# INTERFACE.net
KiCad netlist of a schematic drawn in EAGLE
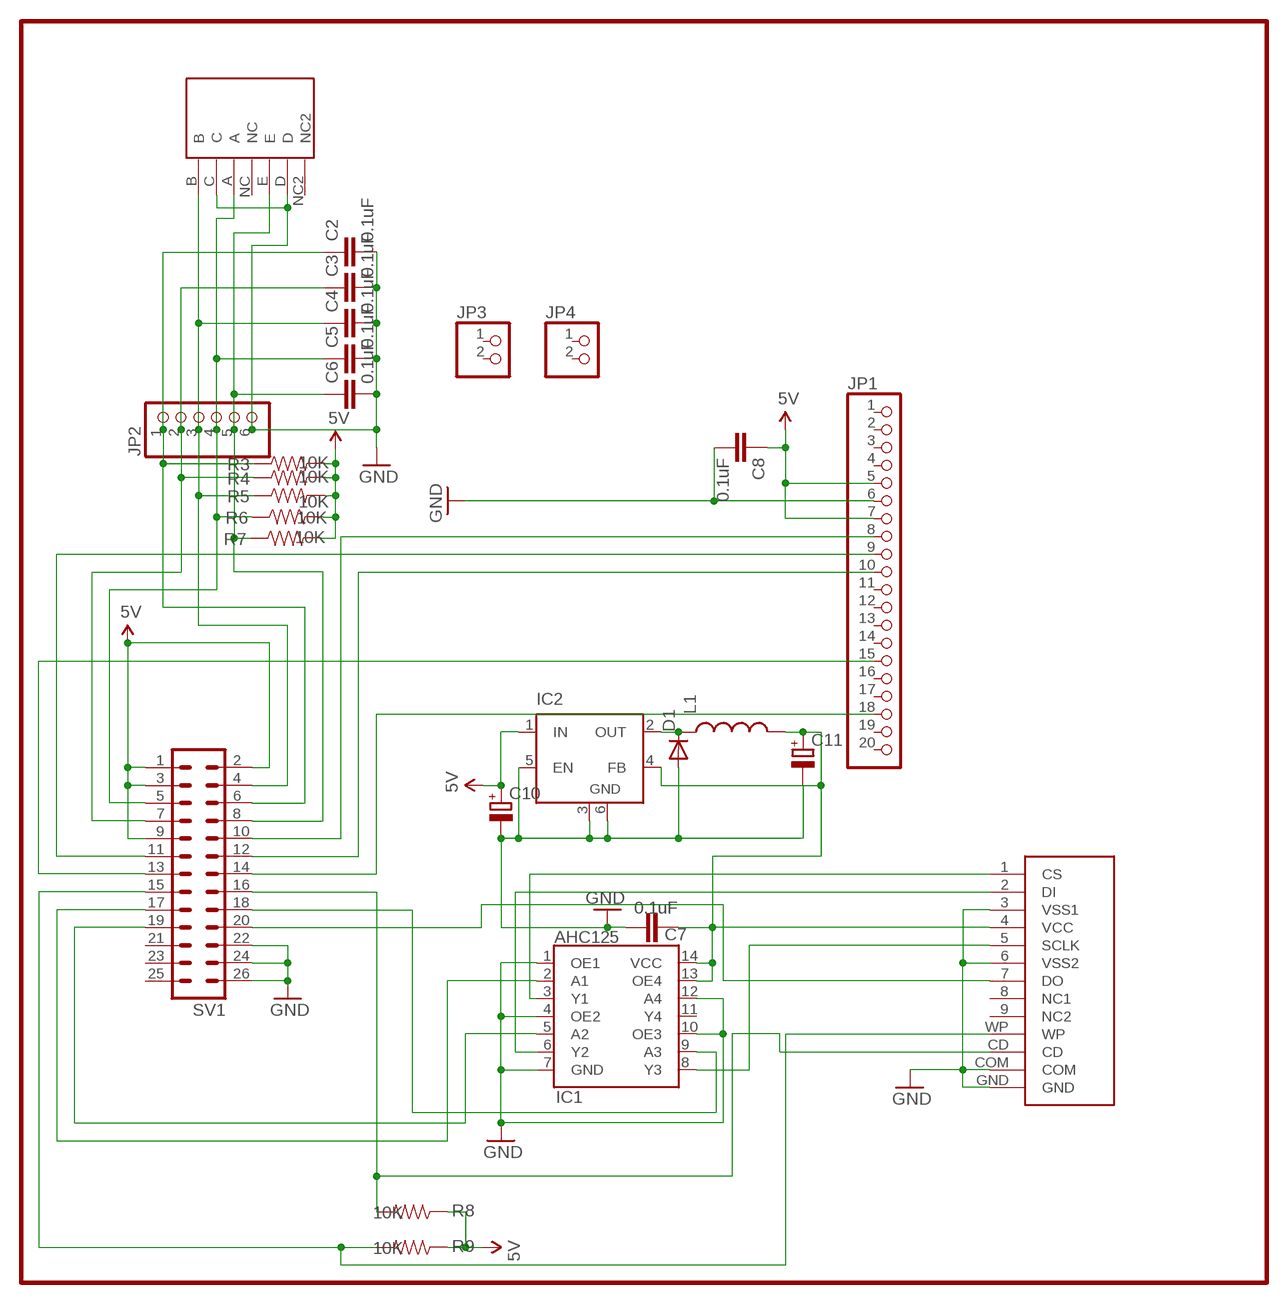
[diagram p0: schematic, sheet 1]

(export (version "E")
  (design (tool "Eeschema 10.0.6"))
  (components
    (comp (ref "C2")
      (value "0.1uF")
      (footprint "eagle-import:0805")
      (libsource (lib "eagle-import") (part "CAP0805"))
    )
    (comp (ref "C3")
      (value "0.1uF")
      (footprint "eagle-import:0805")
      (libsource (lib "eagle-import") (part "CAP0805"))
    )
    (comp (ref "C4")
      (value "0.1uF")
      (footprint "eagle-import:0805")
      (libsource (lib "eagle-import") (part "CAP0805"))
    )
    (comp (ref "C5")
      (value "0.1uF")
      (footprint "eagle-import:0805")
      (libsource (lib "eagle-import") (part "CAP0805"))
    )
    (comp (ref "C6")
      (value "0.1uF")
      (footprint "eagle-import:0805")
      (libsource (lib "eagle-import") (part "CAP0805"))
    )
    (comp (ref "C7")
      (value "0.1uF")
      (footprint "eagle-import:0805")
      (libsource (lib "eagle-import") (part "CAP0805"))
    )
    (comp (ref "C8")
      (value "0.1uF")
      (footprint "eagle-import:0805")
      (libsource (lib "eagle-import") (part "CAP0805"))
    )
    (comp (ref "C10")
      (value "CPOL-EUE3.5-8")
      (footprint "eagle-import:E3,5-8")
      (libsource (lib "eagle-import") (part "CPOL-EUE3.5-8"))
    )
    (comp (ref "C11")
      (value "CPOL-EUE3.5-8")
      (footprint "eagle-import:E3,5-8")
      (libsource (lib "eagle-import") (part "CPOL-EUE3.5-8"))
    )
    (comp (ref "D1")
      (value "DIODESMB")
      (footprint "eagle-import:SMB-DIODE")
      (libsource (lib "eagle-import") (part "DIODESMB"))
    )
    (comp (ref "IC1")
      (value "AHC125")
      (footprint "eagle-import:DIN14")
      (libsource (lib "eagle-import") (part "AHC125"))
    )
    (comp (ref "IC2")
      (value "LM2596S")
      (footprint "eagle-import:TO263-5")
      (libsource (lib "eagle-import") (part "LM2596S"))
    )
    (comp (ref "JP1")
      (value "PINHD-1X20")
      (footprint "eagle-import:1X20")
      (libsource (lib "eagle-import") (part "PINHD-1X20"))
    )
    (comp (ref "JP2")
      (value "PINHD-1X6")
      (footprint "eagle-import:1X06")
      (libsource (lib "eagle-import") (part "PINHD-1X6"))
    )
    (comp (ref "JP3")
      (value "PINHD-1X2")
      (footprint "eagle-import:1X02")
      (libsource (lib "eagle-import") (part "PINHD-1X2"))
    )
    (comp (ref "JP4")
      (value "PINHD-1X2")
      (footprint "eagle-import:1X02")
      (libsource (lib "eagle-import") (part "PINHD-1X2"))
    )
    (comp (ref "L1")
      (value "INDUCTORPWR")
      (footprint "eagle-import:CDRH125")
      (libsource (lib "eagle-import") (part "INDUCTORPWR"))
    )
    (comp (ref "Q2")
      (value "SDCARD")
      (footprint "eagle-import:SDCARD")
      (libsource (lib "eagle-import") (part "SDCARD"))
    )
    (comp (ref "R3")
      (value "10K")
      (footprint "eagle-import:0805")
      (libsource (lib "eagle-import") (part "RESISTOR"))
    )
    (comp (ref "R4")
      (value "10K")
      (footprint "eagle-import:0805")
      (libsource (lib "eagle-import") (part "RESISTOR"))
    )
    (comp (ref "R5")
      (value "10K")
      (footprint "eagle-import:0805")
      (libsource (lib "eagle-import") (part "RESISTOR"))
    )
    (comp (ref "R6")
      (value "10K")
      (footprint "eagle-import:0805")
      (libsource (lib "eagle-import") (part "RESISTOR"))
    )
    (comp (ref "R7")
      (value "10K")
      (footprint "eagle-import:0805")
      (libsource (lib "eagle-import") (part "RESISTOR"))
    )
    (comp (ref "R8")
      (value "10K")
      (footprint "eagle-import:0805")
      (libsource (lib "eagle-import") (part "RESISTOR"))
    )
    (comp (ref "R9")
      (value "10K")
      (footprint "eagle-import:0805")
      (libsource (lib "eagle-import") (part "RESISTOR"))
    )
    (comp (ref "S2")
      (value "DJFS")
      (footprint "eagle-import:PIN5")
      (libsource (lib "eagle-import") (part "DJFS"))
    )
    (comp (ref "SV1")
      (value "ML26")
      (footprint "eagle-import:ML26")
      (libsource (lib "eagle-import") (part "ML26"))
    )
  )
  (nets
    (net (code "1") (name "5V") (class "Default")
      (node (ref "C10") (pin "+") (pinfunction "+_+") (pintype "passive"))
      (node (ref "C8") (pin "1") (pinfunction "1_1") (pintype "passive"))
      (node (ref "IC2") (pin "1") (pinfunction "IN_1") (pintype "input"))
      (node (ref "JP1") (pin "5") (pinfunction "5_5") (pintype "passive"))
      (node (ref "JP1") (pin "7") (pinfunction "7_7") (pintype "passive"))
      (node (ref "R3") (pin "2") (pinfunction "2_2") (pintype "passive"))
      (node (ref "R4") (pin "2") (pinfunction "2_2") (pintype "passive"))
      (node (ref "R5") (pin "2") (pinfunction "2_2") (pintype "passive"))
      (node (ref "R6") (pin "2") (pinfunction "2_2") (pintype "passive"))
      (node (ref "R7") (pin "2") (pinfunction "2_2") (pintype "passive"))
      (node (ref "R8") (pin "1") (pinfunction "1_1") (pintype "passive"))
      (node (ref "R9") (pin "1") (pinfunction "1_1") (pintype "passive"))
      (node (ref "SV1") (pin "1") (pinfunction "1_1") (pintype "passive"))
      (node (ref "SV1") (pin "2") (pinfunction "2_2") (pintype "passive"))
      (node (ref "SV1") (pin "3") (pinfunction "3_3") (pintype "passive"))
      (node (ref "SV1") (pin "9") (pinfunction "9_9") (pintype "passive"))
    )
    (net (code "2") (name "GND") (class "Default")
      (node (ref "C10") (pin "-") (pinfunction "-_-") (pintype "passive"))
      (node (ref "C11") (pin "-") (pinfunction "-_-") (pintype "passive"))
      (node (ref "C2") (pin "2") (pinfunction "2_2") (pintype "passive"))
      (node (ref "C3") (pin "2") (pinfunction "2_2") (pintype "passive"))
      (node (ref "C4") (pin "2") (pinfunction "2_2") (pintype "passive"))
      (node (ref "C5") (pin "2") (pinfunction "2_2") (pintype "passive"))
      (node (ref "C6") (pin "2") (pinfunction "2_2") (pintype "passive"))
      (node (ref "C7") (pin "2") (pinfunction "2_2") (pintype "passive"))
      (node (ref "C8") (pin "2") (pinfunction "2_2") (pintype "passive"))
      (node (ref "D1") (pin "A") (pinfunction "A_A") (pintype "passive"))
      (node (ref "IC1") (pin "1") (pinfunction "OE1_1") (pintype "input"))
      (node (ref "IC1") (pin "10") (pinfunction "OE3_10") (pintype "input"))
      (node (ref "IC1") (pin "12") (pinfunction "A4_12") (pintype "input"))
      (node (ref "IC1") (pin "4") (pinfunction "OE2_4") (pintype "input"))
      (node (ref "IC1") (pin "7") (pinfunction "GND_7") (pintype "power_in"))
      (node (ref "IC2") (pin "3") (pinfunction "GND_3") (pintype "power_in"))
      (node (ref "IC2") (pin "5") (pinfunction "EN_5") (pintype "input"))
      (node (ref "IC2") (pin "6") (pinfunction "GND_6") (pintype "power_in"))
      (node (ref "JP1") (pin "6") (pinfunction "6_6") (pintype "passive"))
      (node (ref "JP2") (pin "6") (pinfunction "6_6") (pintype "passive"))
      (node (ref "Q2") (pin "3") (pinfunction "VSS1_3") (pintype "bidirectional"))
      (node (ref "Q2") (pin "6") (pinfunction "VSS2_6") (pintype "bidirectional"))
      (node (ref "Q2") (pin "COM") (pinfunction "COM_COM") (pintype "bidirectional"))
      (node (ref "Q2") (pin "GND") (pinfunction "GND_GND") (pintype "power_in"))
      (node (ref "S2") (pin "C") (pinfunction "C_C") (pintype "bidirectional"))
      (node (ref "S2") (pin "D") (pinfunction "D_D") (pintype "bidirectional"))
      (node (ref "SV1") (pin "22") (pinfunction "22_22") (pintype "passive"))
      (node (ref "SV1") (pin "24") (pinfunction "24_24") (pintype "passive"))
      (node (ref "SV1") (pin "26") (pinfunction "26_26") (pintype "passive"))
    )
    (net (code "3") (name "Net-(C2-Pad1)") (class "Default")
      (node (ref "C2") (pin "1") (pinfunction "1_1") (pintype "passive"))
      (node (ref "JP2") (pin "1") (pinfunction "1_1") (pintype "passive"))
      (node (ref "R3") (pin "1") (pinfunction "1_1") (pintype "passive"))
      (node (ref "SV1") (pin "6") (pinfunction "6_6") (pintype "passive"))
    )
    (net (code "4") (name "Net-(C3-Pad1)") (class "Default")
      (node (ref "C3") (pin "1") (pinfunction "1_1") (pintype "passive"))
      (node (ref "JP2") (pin "2") (pinfunction "2_2") (pintype "passive"))
      (node (ref "R4") (pin "1") (pinfunction "1_1") (pintype "passive"))
      (node (ref "SV1") (pin "7") (pinfunction "7_7") (pintype "passive"))
    )
    (net (code "5") (name "Net-(C4-Pad1)") (class "Default")
      (node (ref "C4") (pin "1") (pinfunction "1_1") (pintype "passive"))
      (node (ref "JP2") (pin "3") (pinfunction "3_3") (pintype "passive"))
      (node (ref "R5") (pin "1") (pinfunction "1_1") (pintype "passive"))
      (node (ref "S2") (pin "B") (pinfunction "B_B") (pintype "bidirectional"))
      (node (ref "SV1") (pin "4") (pinfunction "4_4") (pintype "passive"))
    )
    (net (code "6") (name "Net-(C5-Pad1)") (class "Default")
      (node (ref "C5") (pin "1") (pinfunction "1_1") (pintype "passive"))
      (node (ref "JP2") (pin "4") (pinfunction "4_4") (pintype "passive"))
      (node (ref "R6") (pin "1") (pinfunction "1_1") (pintype "passive"))
      (node (ref "S2") (pin "A") (pinfunction "A_A") (pintype "bidirectional"))
      (node (ref "SV1") (pin "5") (pinfunction "5_5") (pintype "passive"))
    )
    (net (code "7") (name "Net-(C6-Pad1)") (class "Default")
      (node (ref "C6") (pin "1") (pinfunction "1_1") (pintype "passive"))
      (node (ref "JP2") (pin "5") (pinfunction "5_5") (pintype "passive"))
      (node (ref "R7") (pin "1") (pinfunction "1_1") (pintype "passive"))
      (node (ref "S2") (pin "E") (pinfunction "E_E") (pintype "bidirectional"))
      (node (ref "SV1") (pin "8") (pinfunction "8_8") (pintype "passive"))
    )
    (net (code "8") (name "Net-(IC1-A1)") (class "Default")
      (node (ref "IC1") (pin "2") (pinfunction "A1_2") (pintype "input"))
      (node (ref "SV1") (pin "17") (pinfunction "17_17") (pintype "passive"))
    )
    (net (code "9") (name "Net-(IC1-A2)") (class "Default")
      (node (ref "IC1") (pin "5") (pinfunction "A2_5") (pintype "input"))
      (node (ref "SV1") (pin "19") (pinfunction "19_19") (pintype "passive"))
    )
    (net (code "10") (name "Net-(IC1-A3)") (class "Default")
      (node (ref "IC1") (pin "9") (pinfunction "A3_9") (pintype "input"))
      (node (ref "SV1") (pin "18") (pinfunction "18_18") (pintype "passive"))
    )
    (net (code "11") (name "Net-(IC1-OE4)") (class "Default")
      (node (ref "C11") (pin "+") (pinfunction "+_+") (pintype "passive"))
      (node (ref "C7") (pin "1") (pinfunction "1_1") (pintype "passive"))
      (node (ref "IC1") (pin "13") (pinfunction "OE4_13") (pintype "input"))
      (node (ref "IC1") (pin "14") (pinfunction "VCC_14") (pintype "power_in"))
      (node (ref "IC2") (pin "4") (pinfunction "FB_4") (pintype "input"))
      (node (ref "L1") (pin "2") (pinfunction "2_2") (pintype "passive"))
      (node (ref "Q2") (pin "4") (pinfunction "VCC_4") (pintype "power_in"))
    )
    (net (code "12") (name "Net-(IC1-Y1)") (class "Default")
      (node (ref "IC1") (pin "3") (pinfunction "Y1_3") (pintype "output"))
      (node (ref "Q2") (pin "1") (pinfunction "CS_1") (pintype "bidirectional"))
    )
    (net (code "13") (name "Net-(IC1-Y2)") (class "Default")
      (node (ref "IC1") (pin "6") (pinfunction "Y2_6") (pintype "output"))
      (node (ref "Q2") (pin "2") (pinfunction "DI_2") (pintype "bidirectional"))
    )
    (net (code "14") (name "Net-(IC1-Y3)") (class "Default")
      (node (ref "IC1") (pin "8") (pinfunction "Y3_8") (pintype "output"))
      (node (ref "Q2") (pin "5") (pinfunction "SCLK_5") (pintype "bidirectional"))
    )
    (net (code "15") (name "Net-(IC2-OUT)") (class "Default")
      (node (ref "D1") (pin "C") (pinfunction "C_C") (pintype "passive"))
      (node (ref "IC2") (pin "2") (pinfunction "OUT_2") (pintype "output"))
      (node (ref "L1") (pin "1") (pinfunction "1_1") (pintype "passive"))
    )
    (net (code "16") (name "Net-(JP1-Pad8)") (class "Default")
      (node (ref "JP1") (pin "8") (pinfunction "8_8") (pintype "passive"))
      (node (ref "SV1") (pin "10") (pinfunction "10_10") (pintype "passive"))
    )
    (net (code "17") (name "Net-(JP1-Pad9)") (class "Default")
      (node (ref "JP1") (pin "9") (pinfunction "9_9") (pintype "passive"))
      (node (ref "SV1") (pin "11") (pinfunction "11_11") (pintype "passive"))
    )
    (net (code "18") (name "Net-(JP1-Pad10)") (class "Default")
      (node (ref "JP1") (pin "10") (pinfunction "10_10") (pintype "passive"))
      (node (ref "SV1") (pin "12") (pinfunction "12_12") (pintype "passive"))
    )
    (net (code "19") (name "Net-(JP1-Pad15)") (class "Default")
      (node (ref "JP1") (pin "15") (pinfunction "15_15") (pintype "passive"))
      (node (ref "SV1") (pin "13") (pinfunction "13_13") (pintype "passive"))
    )
    (net (code "20") (name "Net-(JP1-Pad18)") (class "Default")
      (node (ref "JP1") (pin "18") (pinfunction "18_18") (pintype "passive"))
      (node (ref "SV1") (pin "14") (pinfunction "14_14") (pintype "passive"))
    )
    (net (code "21") (name "Net-(Q2-DO)") (class "Default")
      (node (ref "Q2") (pin "7") (pinfunction "DO_7") (pintype "bidirectional"))
      (node (ref "SV1") (pin "20") (pinfunction "20_20") (pintype "passive"))
    )
    (net (code "22") (name "Net-(Q2-PadCD)") (class "Default")
      (node (ref "Q2") (pin "CD") (pinfunction "CD_CD") (pintype "bidirectional"))
      (node (ref "R8") (pin "2") (pinfunction "2_2") (pintype "passive"))
      (node (ref "SV1") (pin "16") (pinfunction "16_16") (pintype "passive"))
    )
    (net (code "23") (name "Net-(Q2-PadWP)") (class "Default")
      (node (ref "Q2") (pin "WP") (pinfunction "WP_WP") (pintype "bidirectional"))
      (node (ref "R9") (pin "2") (pinfunction "2_2") (pintype "passive"))
      (node (ref "SV1") (pin "15") (pinfunction "15_15") (pintype "passive"))
    )
    (net (code "24") (name "unconnected-(IC1-Y4-Pad11)") (class "Default")
      (node (ref "IC1") (pin "11") (pinfunction "Y4_11") (pintype "output"))
    )
    (net (code "25") (name "unconnected-(JP1-Pad1)") (class "Default")
      (node (ref "JP1") (pin "1") (pinfunction "1_1") (pintype "passive"))
    )
    (net (code "26") (name "unconnected-(JP1-Pad2)") (class "Default")
      (node (ref "JP1") (pin "2") (pinfunction "2_2") (pintype "passive"))
    )
    (net (code "27") (name "unconnected-(JP1-Pad3)") (class "Default")
      (node (ref "JP1") (pin "3") (pinfunction "3_3") (pintype "passive"))
    )
    (net (code "28") (name "unconnected-(JP1-Pad4)") (class "Default")
      (node (ref "JP1") (pin "4") (pinfunction "4_4") (pintype "passive"))
    )
    (net (code "29") (name "unconnected-(JP1-Pad11)") (class "Default")
      (node (ref "JP1") (pin "11") (pinfunction "11_11") (pintype "passive"))
    )
    (net (code "30") (name "unconnected-(JP1-Pad12)") (class "Default")
      (node (ref "JP1") (pin "12") (pinfunction "12_12") (pintype "passive"))
    )
    (net (code "31") (name "unconnected-(JP1-Pad13)") (class "Default")
      (node (ref "JP1") (pin "13") (pinfunction "13_13") (pintype "passive"))
    )
    (net (code "32") (name "unconnected-(JP1-Pad14)") (class "Default")
      (node (ref "JP1") (pin "14") (pinfunction "14_14") (pintype "passive"))
    )
    (net (code "33") (name "unconnected-(JP1-Pad16)") (class "Default")
      (node (ref "JP1") (pin "16") (pinfunction "16_16") (pintype "passive"))
    )
    (net (code "34") (name "unconnected-(JP1-Pad17)") (class "Default")
      (node (ref "JP1") (pin "17") (pinfunction "17_17") (pintype "passive"))
    )
    (net (code "35") (name "unconnected-(JP1-Pad19)") (class "Default")
      (node (ref "JP1") (pin "19") (pinfunction "19_19") (pintype "passive"))
    )
    (net (code "36") (name "unconnected-(JP1-Pad20)") (class "Default")
      (node (ref "JP1") (pin "20") (pinfunction "20_20") (pintype "passive"))
    )
    (net (code "37") (name "unconnected-(JP3-Pad1)") (class "Default")
      (node (ref "JP3") (pin "1") (pinfunction "1_1") (pintype "passive"))
    )
    (net (code "38") (name "unconnected-(JP3-Pad2)") (class "Default")
      (node (ref "JP3") (pin "2") (pinfunction "2_2") (pintype "passive"))
    )
    (net (code "39") (name "unconnected-(JP4-Pad1)") (class "Default")
      (node (ref "JP4") (pin "1") (pinfunction "1_1") (pintype "passive"))
    )
    (net (code "40") (name "unconnected-(JP4-Pad2)") (class "Default")
      (node (ref "JP4") (pin "2") (pinfunction "2_2") (pintype "passive"))
    )
    (net (code "41") (name "unconnected-(Q2-NC1-Pad8)") (class "Default")
      (node (ref "Q2") (pin "8") (pinfunction "NC1_8") (pintype "bidirectional"))
    )
    (net (code "42") (name "unconnected-(Q2-NC2-Pad9)") (class "Default")
      (node (ref "Q2") (pin "9") (pinfunction "NC2_9") (pintype "bidirectional"))
    )
    (net (code "43") (name "unconnected-(S2-PadNC)") (class "Default")
      (node (ref "S2") (pin "NC") (pinfunction "NC_NC") (pintype "no_connect"))
    )
    (net (code "44") (name "unconnected-(S2-PadNC2)") (class "Default")
      (node (ref "S2") (pin "NC2") (pinfunction "NC2_NC2") (pintype "no_connect"))
    )
    (net (code "45") (name "unconnected-(SV1-Pad21)") (class "Default")
      (node (ref "SV1") (pin "21") (pinfunction "21_21") (pintype "passive"))
    )
    (net (code "46") (name "unconnected-(SV1-Pad23)") (class "Default")
      (node (ref "SV1") (pin "23") (pinfunction "23_23") (pintype "passive"))
    )
    (net (code "47") (name "unconnected-(SV1-Pad25)") (class "Default")
      (node (ref "SV1") (pin "25") (pinfunction "25_25") (pintype "passive"))
    )
  )
)
